# ina_extension_jack_motor_schematic.net
KiCad netlist of a schematic drawn in Altium Designer
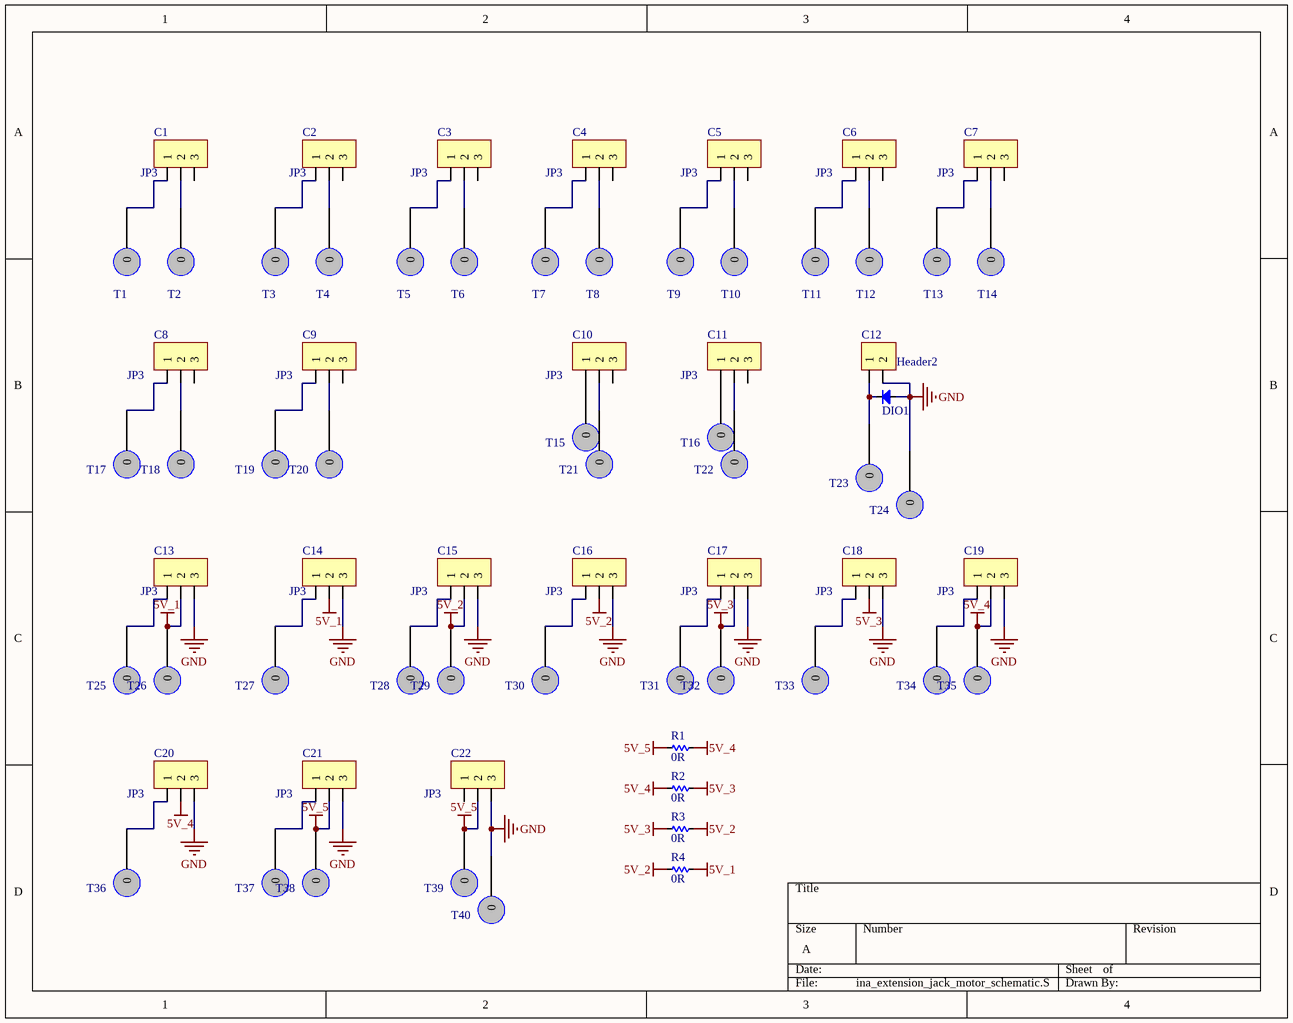
[diagram p0: ina_extension_jack_motor_schematic.SchDoc]

(export (version "E")
  (design (tool "Eeschema 10.0.6"))
  (components
    (comp (ref "C1")
      (value "JP3")
      (footprint "JP3-D1T")
      (description "WR-PHD 2.54 mm Angled Socket Header")
      (fields
        (field (name "MANUFACTURER") "Würth Elektronik eiSos GmbH")
        (field (name "PARTNO") "613003143121")
        (field (name "CREATED BY") "Karrer Zheng")
      )
      (libsource (lib "LIBRARY") (part "JP3"))
    )
    (comp (ref "C2")
      (value "JP3")
      (footprint "JP3-D1T")
      (description "WR-PHD 2.54 mm Angled Socket Header")
      (fields
        (field (name "MANUFACTURER") "Würth Elektronik eiSos GmbH")
        (field (name "PARTNO") "613003143121")
        (field (name "CREATED BY") "Karrer Zheng")
      )
      (libsource (lib "LIBRARY") (part "JP3"))
    )
    (comp (ref "C3")
      (value "JP3")
      (footprint "JP3-D1T")
      (description "WR-PHD 2.54 mm Angled Socket Header")
      (fields
        (field (name "MANUFACTURER") "Würth Elektronik eiSos GmbH")
        (field (name "PARTNO") "613003143121")
        (field (name "CREATED BY") "Karrer Zheng")
      )
      (libsource (lib "LIBRARY") (part "JP3"))
    )
    (comp (ref "C4")
      (value "JP3")
      (footprint "JP3-D1T")
      (description "WR-PHD 2.54 mm Angled Socket Header")
      (fields
        (field (name "MANUFACTURER") "Würth Elektronik eiSos GmbH")
        (field (name "PARTNO") "613003143121")
        (field (name "CREATED BY") "Karrer Zheng")
      )
      (libsource (lib "LIBRARY") (part "JP3"))
    )
    (comp (ref "C5")
      (value "JP3")
      (footprint "JP3-D1T")
      (description "WR-PHD 2.54 mm Angled Socket Header")
      (fields
        (field (name "MANUFACTURER") "Würth Elektronik eiSos GmbH")
        (field (name "PARTNO") "613003143121")
        (field (name "CREATED BY") "Karrer Zheng")
      )
      (libsource (lib "LIBRARY") (part "JP3"))
    )
    (comp (ref "C6")
      (value "JP3")
      (footprint "JP3-D1T")
      (description "WR-PHD 2.54 mm Angled Socket Header")
      (fields
        (field (name "MANUFACTURER") "Würth Elektronik eiSos GmbH")
        (field (name "PARTNO") "613003143121")
        (field (name "CREATED BY") "Karrer Zheng")
      )
      (libsource (lib "LIBRARY") (part "JP3"))
    )
    (comp (ref "C7")
      (value "JP3")
      (footprint "JP3-D1T")
      (description "WR-PHD 2.54 mm Angled Socket Header")
      (fields
        (field (name "MANUFACTURER") "Würth Elektronik eiSos GmbH")
        (field (name "PARTNO") "613003143121")
        (field (name "CREATED BY") "Karrer Zheng")
      )
      (libsource (lib "LIBRARY") (part "JP3"))
    )
    (comp (ref "C8")
      (value "JP3")
      (footprint "JP3-D1T")
      (description "WR-PHD 2.54 mm Angled Socket Header")
      (fields
        (field (name "MANUFACTURER") "Würth Elektronik eiSos GmbH")
        (field (name "PARTNO") "613003143121")
        (field (name "CREATED BY") "Karrer Zheng")
      )
      (libsource (lib "LIBRARY") (part "JP3"))
    )
    (comp (ref "C9")
      (value "JP3")
      (footprint "JP3-D1T")
      (description "WR-PHD 2.54 mm Angled Socket Header")
      (fields
        (field (name "MANUFACTURER") "Würth Elektronik eiSos GmbH")
        (field (name "PARTNO") "613003143121")
        (field (name "CREATED BY") "Karrer Zheng")
      )
      (libsource (lib "LIBRARY") (part "JP3"))
    )
    (comp (ref "C10")
      (value "JP3")
      (footprint "JP3-D1T")
      (description "WR-PHD 2.54 mm Angled Socket Header")
      (fields
        (field (name "MANUFACTURER") "Würth Elektronik eiSos GmbH")
        (field (name "PARTNO") "613003143121")
        (field (name "CREATED BY") "Karrer Zheng")
      )
      (libsource (lib "LIBRARY") (part "JP3"))
    )
    (comp (ref "C11")
      (value "JP3")
      (footprint "JP3-D1T")
      (description "WR-PHD 2.54 mm Angled Socket Header")
      (fields
        (field (name "MANUFACTURER") "Würth Elektronik eiSos GmbH")
        (field (name "PARTNO") "613003143121")
        (field (name "CREATED BY") "Karrer Zheng")
      )
      (libsource (lib "LIBRARY") (part "JP3"))
    )
    (comp (ref "C12")
      (value "Header2")
      (footprint "Header2")
      (description "Header IDC, 2 x 1 Pin Vertical 2.54mm Pitch (Non-Boxed, Male)")
      (fields
        (field (name "MANUFACTURER") "Würth Elektronik eiSos GmbH")
        (field (name "PARTNO") "613002143121")
        (field (name "CREATED BY") "Karrer Zheng")
      )
      (libsource (lib "LIBRARY") (part "Header2"))
    )
    (comp (ref "C13")
      (value "JP3")
      (footprint "JP3-D1T")
      (description "WR-PHD 2.54 mm Angled Socket Header")
      (fields
        (field (name "MANUFACTURER") "Würth Elektronik eiSos GmbH")
        (field (name "PARTNO") "613003143121")
        (field (name "CREATED BY") "Karrer Zheng")
      )
      (libsource (lib "LIBRARY") (part "JP3"))
    )
    (comp (ref "C14")
      (value "JP3")
      (footprint "JP3-D1T")
      (description "WR-PHD 2.54 mm Angled Socket Header")
      (fields
        (field (name "MANUFACTURER") "Würth Elektronik eiSos GmbH")
        (field (name "PARTNO") "613003143121")
        (field (name "CREATED BY") "Karrer Zheng")
      )
      (libsource (lib "LIBRARY") (part "JP3"))
    )
    (comp (ref "C15")
      (value "JP3")
      (footprint "JP3-D1T")
      (description "WR-PHD 2.54 mm Angled Socket Header")
      (fields
        (field (name "MANUFACTURER") "Würth Elektronik eiSos GmbH")
        (field (name "PARTNO") "613003143121")
        (field (name "CREATED BY") "Karrer Zheng")
      )
      (libsource (lib "LIBRARY") (part "JP3"))
    )
    (comp (ref "C16")
      (value "JP3")
      (footprint "JP3-D1T")
      (description "WR-PHD 2.54 mm Angled Socket Header")
      (fields
        (field (name "MANUFACTURER") "Würth Elektronik eiSos GmbH")
        (field (name "PARTNO") "613003143121")
        (field (name "CREATED BY") "Karrer Zheng")
      )
      (libsource (lib "LIBRARY") (part "JP3"))
    )
    (comp (ref "C17")
      (value "JP3")
      (footprint "JP3-D1T")
      (description "WR-PHD 2.54 mm Angled Socket Header")
      (fields
        (field (name "MANUFACTURER") "Würth Elektronik eiSos GmbH")
        (field (name "PARTNO") "613003143121")
        (field (name "CREATED BY") "Karrer Zheng")
      )
      (libsource (lib "LIBRARY") (part "JP3"))
    )
    (comp (ref "C18")
      (value "JP3")
      (footprint "JP3-D1T")
      (description "WR-PHD 2.54 mm Angled Socket Header")
      (fields
        (field (name "MANUFACTURER") "Würth Elektronik eiSos GmbH")
        (field (name "PARTNO") "613003143121")
        (field (name "CREATED BY") "Karrer Zheng")
      )
      (libsource (lib "LIBRARY") (part "JP3"))
    )
    (comp (ref "C19")
      (value "JP3")
      (footprint "JP3-D1T")
      (description "WR-PHD 2.54 mm Angled Socket Header")
      (fields
        (field (name "MANUFACTURER") "Würth Elektronik eiSos GmbH")
        (field (name "PARTNO") "613003143121")
        (field (name "CREATED BY") "Karrer Zheng")
      )
      (libsource (lib "LIBRARY") (part "JP3"))
    )
    (comp (ref "C20")
      (value "JP3")
      (footprint "JP3-D1T")
      (description "WR-PHD 2.54 mm Angled Socket Header")
      (fields
        (field (name "MANUFACTURER") "Würth Elektronik eiSos GmbH")
        (field (name "PARTNO") "613003143121")
        (field (name "CREATED BY") "Karrer Zheng")
      )
      (libsource (lib "LIBRARY") (part "JP3"))
    )
    (comp (ref "C21")
      (value "JP3")
      (footprint "JP3-D1T")
      (description "WR-PHD 2.54 mm Angled Socket Header")
      (fields
        (field (name "MANUFACTURER") "Würth Elektronik eiSos GmbH")
        (field (name "PARTNO") "613003143121")
        (field (name "CREATED BY") "Karrer Zheng")
      )
      (libsource (lib "LIBRARY") (part "JP3"))
    )
    (comp (ref "C22")
      (value "JP3")
      (footprint "JP3-D1T")
      (description "WR-PHD 2.54 mm Angled Socket Header")
      (fields
        (field (name "MANUFACTURER") "Würth Elektronik eiSos GmbH")
        (field (name "PARTNO") "613003143121")
        (field (name "CREATED BY") "Karrer Zheng")
      )
      (libsource (lib "LIBRARY") (part "JP3"))
    )
    (comp (ref "DIO1")
      (value "Diode SMD")
      (footprint "DIO-SMD-123")
      (description "Default Diode")
      (fields (field (name "PUBLISHER") "Altium Limited"))
      (libsource (lib "LIBRARY") (part "Diode SMD"))
    )
    (comp (ref "R1")
      (value "0R")
      (footprint "RES-SMD-0603")
      (description "Resistor")
      (fields
        (field (name "MANUFACTURER") "Generic Components")
        (field (name "PUBLISHER") "Altium Hobart Technology Centre")
      )
      (libsource (lib "LIBRARY") (part "Res-SMD"))
    )
    (comp (ref "R2")
      (value "0R")
      (footprint "RES-SMD-0603")
      (description "Resistor")
      (fields
        (field (name "MANUFACTURER") "Generic Components")
        (field (name "PUBLISHER") "Altium Hobart Technology Centre")
      )
      (libsource (lib "LIBRARY") (part "Res-SMD"))
    )
    (comp (ref "R3")
      (value "0R")
      (footprint "RES-SMD-0603")
      (description "Resistor")
      (fields
        (field (name "MANUFACTURER") "Generic Components")
        (field (name "PUBLISHER") "Altium Hobart Technology Centre")
      )
      (libsource (lib "LIBRARY") (part "Res-SMD"))
    )
    (comp (ref "R4")
      (value "0R")
      (footprint "RES-SMD-0603")
      (description "Resistor")
      (fields
        (field (name "MANUFACTURER") "Generic Components")
        (field (name "PUBLISHER") "Altium Hobart Technology Centre")
      )
      (libsource (lib "LIBRARY") (part "Res-SMD"))
    )
    (comp (ref "T1")
      (value "Pad")
      (footprint "pad_ina:PCBComponent_1")
      (description "pad")
      (libsource (lib "pad_ina") (part "Component_1"))
    )
    (comp (ref "T2")
      (value "Pad")
      (footprint "pad_ina:PCBComponent_1")
      (description "pad")
      (libsource (lib "pad_ina") (part "Component_1"))
    )
    (comp (ref "T3")
      (value "Pad")
      (footprint "pad_ina:PCBComponent_1")
      (description "pad")
      (libsource (lib "pad_ina") (part "Component_1"))
    )
    (comp (ref "T4")
      (value "Pad")
      (footprint "pad_ina:PCBComponent_1")
      (description "pad")
      (libsource (lib "pad_ina") (part "Component_1"))
    )
    (comp (ref "T5")
      (value "Pad")
      (footprint "pad_ina:PCBComponent_1")
      (description "pad")
      (libsource (lib "pad_ina") (part "Component_1"))
    )
    (comp (ref "T6")
      (value "Pad")
      (footprint "pad_ina:PCBComponent_1")
      (description "pad")
      (libsource (lib "pad_ina") (part "Component_1"))
    )
    (comp (ref "T7")
      (value "Pad")
      (footprint "pad_ina:PCBComponent_1")
      (description "pad")
      (libsource (lib "pad_ina") (part "Component_1"))
    )
    (comp (ref "T8")
      (value "Pad")
      (footprint "pad_ina:PCBComponent_1")
      (description "pad")
      (libsource (lib "pad_ina") (part "Component_1"))
    )
    (comp (ref "T9")
      (value "Pad")
      (footprint "pad_ina:PCBComponent_1")
      (description "pad")
      (libsource (lib "pad_ina") (part "Component_1"))
    )
    (comp (ref "T10")
      (value "Pad")
      (footprint "pad_ina:PCBComponent_1")
      (description "pad")
      (libsource (lib "pad_ina") (part "Component_1"))
    )
    (comp (ref "T11")
      (value "Pad")
      (footprint "pad_ina:PCBComponent_1")
      (description "pad")
      (libsource (lib "pad_ina") (part "Component_1"))
    )
    (comp (ref "T12")
      (value "Pad")
      (footprint "pad_ina:PCBComponent_1")
      (description "pad")
      (libsource (lib "pad_ina") (part "Component_1"))
    )
    (comp (ref "T13")
      (value "Pad")
      (footprint "pad_ina:PCBComponent_1")
      (description "pad")
      (libsource (lib "pad_ina") (part "Component_1"))
    )
    (comp (ref "T14")
      (value "Pad")
      (footprint "pad_ina:PCBComponent_1")
      (description "pad")
      (libsource (lib "pad_ina") (part "Component_1"))
    )
    (comp (ref "T15")
      (value "Pad")
      (footprint "pad_ina:PCBComponent_1")
      (description "pad")
      (libsource (lib "pad_ina") (part "Component_1"))
    )
    (comp (ref "T16")
      (value "Pad")
      (footprint "pad_ina:PCBComponent_1")
      (description "pad")
      (libsource (lib "pad_ina") (part "Component_1"))
    )
    (comp (ref "T17")
      (value "Pad")
      (footprint "pad_ina:PCBComponent_1")
      (description "pad")
      (libsource (lib "pad_ina") (part "Component_1"))
    )
    (comp (ref "T18")
      (value "Pad")
      (footprint "pad_ina:PCBComponent_1")
      (description "pad")
      (libsource (lib "pad_ina") (part "Component_1"))
    )
    (comp (ref "T19")
      (value "Pad")
      (footprint "pad_ina:PCBComponent_1")
      (description "pad")
      (libsource (lib "pad_ina") (part "Component_1"))
    )
    (comp (ref "T20")
      (value "Pad")
      (footprint "pad_ina:PCBComponent_1")
      (description "pad")
      (libsource (lib "pad_ina") (part "Component_1"))
    )
    (comp (ref "T21")
      (value "Pad")
      (footprint "pad_ina:PCBComponent_1")
      (description "pad")
      (libsource (lib "pad_ina") (part "Component_1"))
    )
    (comp (ref "T22")
      (value "Pad")
      (footprint "pad_ina:PCBComponent_1")
      (description "pad")
      (libsource (lib "pad_ina") (part "Component_1"))
    )
    (comp (ref "T23")
      (value "Pad")
      (footprint "pad_ina:PCBComponent_1")
      (description "pad")
      (libsource (lib "pad_ina") (part "Component_1"))
    )
    (comp (ref "T24")
      (value "Pad")
      (footprint "pad_ina:PCBComponent_1")
      (description "pad")
      (libsource (lib "pad_ina") (part "Component_1"))
    )
    (comp (ref "T25")
      (value "Pad")
      (footprint "pad_ina:PCBComponent_1")
      (description "pad")
      (libsource (lib "pad_ina") (part "Component_1"))
    )
    (comp (ref "T26")
      (value "Pad")
      (footprint "pad_ina:PCBComponent_1")
      (description "pad")
      (libsource (lib "pad_ina") (part "Component_1"))
    )
    (comp (ref "T27")
      (value "Pad")
      (footprint "pad_ina:PCBComponent_1")
      (description "pad")
      (libsource (lib "pad_ina") (part "Component_1"))
    )
    (comp (ref "T28")
      (value "Pad")
      (footprint "pad_ina:PCBComponent_1")
      (description "pad")
      (libsource (lib "pad_ina") (part "Component_1"))
    )
    (comp (ref "T29")
      (value "Pad")
      (footprint "pad_ina:PCBComponent_1")
      (description "pad")
      (libsource (lib "pad_ina") (part "Component_1"))
    )
    (comp (ref "T30")
      (value "Pad")
      (footprint "pad_ina:PCBComponent_1")
      (description "pad")
      (libsource (lib "pad_ina") (part "Component_1"))
    )
    (comp (ref "T31")
      (value "Pad")
      (footprint "pad_ina:PCBComponent_1")
      (description "pad")
      (libsource (lib "pad_ina") (part "Component_1"))
    )
    (comp (ref "T32")
      (value "Pad")
      (footprint "pad_ina:PCBComponent_1")
      (description "pad")
      (libsource (lib "pad_ina") (part "Component_1"))
    )
    (comp (ref "T33")
      (value "Pad")
      (footprint "pad_ina:PCBComponent_1")
      (description "pad")
      (libsource (lib "pad_ina") (part "Component_1"))
    )
    (comp (ref "T34")
      (value "Pad")
      (footprint "pad_ina:PCBComponent_1")
      (description "pad")
      (libsource (lib "pad_ina") (part "Component_1"))
    )
    (comp (ref "T35")
      (value "Pad")
      (footprint "pad_ina:PCBComponent_1")
      (description "pad")
      (libsource (lib "pad_ina") (part "Component_1"))
    )
    (comp (ref "T36")
      (value "Pad")
      (footprint "pad_ina:PCBComponent_1")
      (description "pad")
      (libsource (lib "pad_ina") (part "Component_1"))
    )
    (comp (ref "T37")
      (value "Pad")
      (footprint "pad_ina:PCBComponent_1")
      (description "pad")
      (libsource (lib "pad_ina") (part "Component_1"))
    )
    (comp (ref "T38")
      (value "Pad")
      (footprint "pad_ina:PCBComponent_1")
      (description "pad")
      (libsource (lib "pad_ina") (part "Component_1"))
    )
    (comp (ref "T39")
      (value "Pad")
      (footprint "pad_ina:PCBComponent_1")
      (description "pad")
      (libsource (lib "pad_ina") (part "Component_1"))
    )
    (comp (ref "T40")
      (value "Pad")
      (footprint "pad_ina:PCBComponent_1")
      (description "pad")
      (libsource (lib "pad_ina") (part "Component_1"))
    )
  )
  (nets
    (net (code "1") (name "5V_1") (class "Default")
      (node (ref "C13") (pin "2") (pinfunction "2_2") (pintype "passive"))
      (node (ref "C14") (pin "2") (pinfunction "2_2") (pintype "passive"))
      (node (ref "R4") (pin "2") (pinfunction "2_2") (pintype "passive"))
      (node (ref "T26") (pin "0") (pinfunction "0_0") (pintype "passive"))
    )
    (net (code "2") (name "5V_2") (class "Default")
      (node (ref "C15") (pin "2") (pinfunction "2_2") (pintype "passive"))
      (node (ref "C16") (pin "2") (pinfunction "2_2") (pintype "passive"))
      (node (ref "R3") (pin "2") (pinfunction "2_2") (pintype "passive"))
      (node (ref "R4") (pin "1") (pinfunction "1_1") (pintype "passive"))
      (node (ref "T29") (pin "0") (pinfunction "0_0") (pintype "passive"))
    )
    (net (code "3") (name "5V_3") (class "Default")
      (node (ref "C17") (pin "2") (pinfunction "2_2") (pintype "passive"))
      (node (ref "C18") (pin "2") (pinfunction "2_2") (pintype "passive"))
      (node (ref "R2") (pin "2") (pinfunction "2_2") (pintype "passive"))
      (node (ref "R3") (pin "1") (pinfunction "1_1") (pintype "passive"))
      (node (ref "T32") (pin "0") (pinfunction "0_0") (pintype "passive"))
    )
    (net (code "4") (name "5V_4") (class "Default")
      (node (ref "C19") (pin "2") (pinfunction "2_2") (pintype "passive"))
      (node (ref "C20") (pin "2") (pinfunction "2_2") (pintype "passive"))
      (node (ref "R1") (pin "2") (pinfunction "2_2") (pintype "passive"))
      (node (ref "R2") (pin "1") (pinfunction "1_1") (pintype "passive"))
      (node (ref "T35") (pin "0") (pinfunction "0_0") (pintype "passive"))
    )
    (net (code "5") (name "5V_5") (class "Default")
      (node (ref "C21") (pin "2") (pinfunction "2_2") (pintype "passive"))
      (node (ref "C22") (pin "2") (pinfunction "2_2") (pintype "passive"))
      (node (ref "R1") (pin "1") (pinfunction "1_1") (pintype "passive"))
      (node (ref "T38") (pin "0") (pinfunction "0_0") (pintype "passive"))
      (node (ref "T39") (pin "0") (pinfunction "0_0") (pintype "passive"))
    )
    (net (code "6") (name "GND") (class "Default")
      (node (ref "C12") (pin "2") (pinfunction "2_2") (pintype "passive"))
      (node (ref "C13") (pin "3") (pinfunction "3_3") (pintype "passive"))
      (node (ref "C14") (pin "3") (pinfunction "3_3") (pintype "passive"))
      (node (ref "C15") (pin "3") (pinfunction "3_3") (pintype "passive"))
      (node (ref "C16") (pin "3") (pinfunction "3_3") (pintype "passive"))
      (node (ref "C17") (pin "3") (pinfunction "3_3") (pintype "passive"))
      (node (ref "C18") (pin "3") (pinfunction "3_3") (pintype "passive"))
      (node (ref "C19") (pin "3") (pinfunction "3_3") (pintype "passive"))
      (node (ref "C20") (pin "3") (pinfunction "3_3") (pintype "passive"))
      (node (ref "C21") (pin "3") (pinfunction "3_3") (pintype "passive"))
      (node (ref "C22") (pin "3") (pinfunction "3_3") (pintype "passive"))
      (node (ref "DIO1") (pin "1") (pinfunction "A_1") (pintype "passive"))
      (node (ref "T24") (pin "0") (pinfunction "0_0") (pintype "passive"))
      (node (ref "T40") (pin "0") (pinfunction "0_0") (pintype "passive"))
    )
    (net (code "7") (name "Net-(C1-Pad1)") (class "Default")
      (node (ref "C1") (pin "1") (pinfunction "1_1") (pintype "passive"))
      (node (ref "T1") (pin "0") (pinfunction "0_0") (pintype "passive"))
    )
    (net (code "8") (name "Net-(C1-Pad2)") (class "Default")
      (node (ref "C1") (pin "2") (pinfunction "2_2") (pintype "passive"))
      (node (ref "T2") (pin "0") (pinfunction "0_0") (pintype "passive"))
    )
    (net (code "9") (name "Net-(C2-Pad1)") (class "Default")
      (node (ref "C2") (pin "1") (pinfunction "1_1") (pintype "passive"))
      (node (ref "T3") (pin "0") (pinfunction "0_0") (pintype "passive"))
    )
    (net (code "10") (name "Net-(C2-Pad2)") (class "Default")
      (node (ref "C2") (pin "2") (pinfunction "2_2") (pintype "passive"))
      (node (ref "T4") (pin "0") (pinfunction "0_0") (pintype "passive"))
    )
    (net (code "11") (name "Net-(C3-Pad1)") (class "Default")
      (node (ref "C3") (pin "1") (pinfunction "1_1") (pintype "passive"))
      (node (ref "T5") (pin "0") (pinfunction "0_0") (pintype "passive"))
    )
    (net (code "12") (name "Net-(C3-Pad2)") (class "Default")
      (node (ref "C3") (pin "2") (pinfunction "2_2") (pintype "passive"))
      (node (ref "T6") (pin "0") (pinfunction "0_0") (pintype "passive"))
    )
    (net (code "13") (name "Net-(C4-Pad1)") (class "Default")
      (node (ref "C4") (pin "1") (pinfunction "1_1") (pintype "passive"))
      (node (ref "T7") (pin "0") (pinfunction "0_0") (pintype "passive"))
    )
    (net (code "14") (name "Net-(C4-Pad2)") (class "Default")
      (node (ref "C4") (pin "2") (pinfunction "2_2") (pintype "passive"))
      (node (ref "T8") (pin "0") (pinfunction "0_0") (pintype "passive"))
    )
    (net (code "15") (name "Net-(C5-Pad1)") (class "Default")
      (node (ref "C5") (pin "1") (pinfunction "1_1") (pintype "passive"))
      (node (ref "T9") (pin "0") (pinfunction "0_0") (pintype "passive"))
    )
    (net (code "16") (name "Net-(C5-Pad2)") (class "Default")
      (node (ref "C5") (pin "2") (pinfunction "2_2") (pintype "passive"))
      (node (ref "T10") (pin "0") (pinfunction "0_0") (pintype "passive"))
    )
    (net (code "17") (name "Net-(C6-Pad1)") (class "Default")
      (node (ref "C6") (pin "1") (pinfunction "1_1") (pintype "passive"))
      (node (ref "T11") (pin "0") (pinfunction "0_0") (pintype "passive"))
    )
    (net (code "18") (name "Net-(C6-Pad2)") (class "Default")
      (node (ref "C6") (pin "2") (pinfunction "2_2") (pintype "passive"))
      (node (ref "T12") (pin "0") (pinfunction "0_0") (pintype "passive"))
    )
    (net (code "19") (name "Net-(C7-Pad1)") (class "Default")
      (node (ref "C7") (pin "1") (pinfunction "1_1") (pintype "passive"))
      (node (ref "T13") (pin "0") (pinfunction "0_0") (pintype "passive"))
    )
    (net (code "20") (name "Net-(C7-Pad2)") (class "Default")
      (node (ref "C7") (pin "2") (pinfunction "2_2") (pintype "passive"))
      (node (ref "T14") (pin "0") (pinfunction "0_0") (pintype "passive"))
    )
    (net (code "21") (name "Net-(C8-Pad1)") (class "Default")
      (node (ref "C8") (pin "1") (pinfunction "1_1") (pintype "passive"))
      (node (ref "T17") (pin "0") (pinfunction "0_0") (pintype "passive"))
    )
    (net (code "22") (name "Net-(C8-Pad2)") (class "Default")
      (node (ref "C8") (pin "2") (pinfunction "2_2") (pintype "passive"))
      (node (ref "T18") (pin "0") (pinfunction "0_0") (pintype "passive"))
    )
    (net (code "23") (name "Net-(C9-Pad1)") (class "Default")
      (node (ref "C9") (pin "1") (pinfunction "1_1") (pintype "passive"))
      (node (ref "T19") (pin "0") (pinfunction "0_0") (pintype "passive"))
    )
    (net (code "24") (name "Net-(C9-Pad2)") (class "Default")
      (node (ref "C9") (pin "2") (pinfunction "2_2") (pintype "passive"))
      (node (ref "T20") (pin "0") (pinfunction "0_0") (pintype "passive"))
    )
    (net (code "25") (name "Net-(C10-Pad1)") (class "Default")
      (node (ref "C10") (pin "1") (pinfunction "1_1") (pintype "passive"))
      (node (ref "T15") (pin "0") (pinfunction "0_0") (pintype "passive"))
    )
    (net (code "26") (name "Net-(C10-Pad2)") (class "Default")
      (node (ref "C10") (pin "2") (pinfunction "2_2") (pintype "passive"))
      (node (ref "T21") (pin "0") (pinfunction "0_0") (pintype "passive"))
    )
    (net (code "27") (name "Net-(C11-Pad1)") (class "Default")
      (node (ref "C11") (pin "1") (pinfunction "1_1") (pintype "passive"))
      (node (ref "T16") (pin "0") (pinfunction "0_0") (pintype "passive"))
    )
    (net (code "28") (name "Net-(C11-Pad2)") (class "Default")
      (node (ref "C11") (pin "2") (pinfunction "2_2") (pintype "passive"))
      (node (ref "T22") (pin "0") (pinfunction "0_0") (pintype "passive"))
    )
    (net (code "29") (name "Net-(C13-Pad1)") (class "Default")
      (node (ref "C13") (pin "1") (pinfunction "1_1") (pintype "passive"))
      (node (ref "T25") (pin "0") (pinfunction "0_0") (pintype "passive"))
    )
    (net (code "30") (name "Net-(C14-Pad1)") (class "Default")
      (node (ref "C14") (pin "1") (pinfunction "1_1") (pintype "passive"))
      (node (ref "T27") (pin "0") (pinfunction "0_0") (pintype "passive"))
    )
    (net (code "31") (name "Net-(C15-Pad1)") (class "Default")
      (node (ref "C15") (pin "1") (pinfunction "1_1") (pintype "passive"))
      (node (ref "T28") (pin "0") (pinfunction "0_0") (pintype "passive"))
    )
    (net (code "32") (name "Net-(C16-Pad1)") (class "Default")
      (node (ref "C16") (pin "1") (pinfunction "1_1") (pintype "passive"))
      (node (ref "T30") (pin "0") (pinfunction "0_0") (pintype "passive"))
    )
    (net (code "33") (name "Net-(C17-Pad1)") (class "Default")
      (node (ref "C17") (pin "1") (pinfunction "1_1") (pintype "passive"))
      (node (ref "T31") (pin "0") (pinfunction "0_0") (pintype "passive"))
    )
    (net (code "34") (name "Net-(C18-Pad1)") (class "Default")
      (node (ref "C18") (pin "1") (pinfunction "1_1") (pintype "passive"))
      (node (ref "T33") (pin "0") (pinfunction "0_0") (pintype "passive"))
    )
    (net (code "35") (name "Net-(C19-Pad1)") (class "Default")
      (node (ref "C19") (pin "1") (pinfunction "1_1") (pintype "passive"))
      (node (ref "T34") (pin "0") (pinfunction "0_0") (pintype "passive"))
    )
    (net (code "36") (name "Net-(C20-Pad1)") (class "Default")
      (node (ref "C20") (pin "1") (pinfunction "1_1") (pintype "passive"))
      (node (ref "T36") (pin "0") (pinfunction "0_0") (pintype "passive"))
    )
    (net (code "37") (name "Net-(C21-Pad1)") (class "Default")
      (node (ref "C21") (pin "1") (pinfunction "1_1") (pintype "passive"))
      (node (ref "T37") (pin "0") (pinfunction "0_0") (pintype "passive"))
    )
    (net (code "38") (name "Net-(DIO1-K)") (class "Default")
      (node (ref "C12") (pin "1") (pinfunction "1_1") (pintype "passive"))
      (node (ref "DIO1") (pin "2") (pinfunction "K_2") (pintype "passive"))
      (node (ref "T23") (pin "0") (pinfunction "0_0") (pintype "passive"))
    )
    (net (code "39") (name "unconnected-(C1-Pad3)") (class "Default")
      (node (ref "C1") (pin "3") (pinfunction "3_3") (pintype "passive"))
    )
    (net (code "40") (name "unconnected-(C2-Pad3)") (class "Default")
      (node (ref "C2") (pin "3") (pinfunction "3_3") (pintype "passive"))
    )
    (net (code "41") (name "unconnected-(C3-Pad3)") (class "Default")
      (node (ref "C3") (pin "3") (pinfunction "3_3") (pintype "passive"))
    )
    (net (code "42") (name "unconnected-(C4-Pad3)") (class "Default")
      (node (ref "C4") (pin "3") (pinfunction "3_3") (pintype "passive"))
    )
    (net (code "43") (name "unconnected-(C5-Pad3)") (class "Default")
      (node (ref "C5") (pin "3") (pinfunction "3_3") (pintype "passive"))
    )
    (net (code "44") (name "unconnected-(C6-Pad3)") (class "Default")
      (node (ref "C6") (pin "3") (pinfunction "3_3") (pintype "passive"))
    )
    (net (code "45") (name "unconnected-(C7-Pad3)") (class "Default")
      (node (ref "C7") (pin "3") (pinfunction "3_3") (pintype "passive"))
    )
    (net (code "46") (name "unconnected-(C8-Pad3)") (class "Default")
      (node (ref "C8") (pin "3") (pinfunction "3_3") (pintype "passive"))
    )
    (net (code "47") (name "unconnected-(C9-Pad3)") (class "Default")
      (node (ref "C9") (pin "3") (pinfunction "3_3") (pintype "passive"))
    )
    (net (code "48") (name "unconnected-(C10-Pad3)") (class "Default")
      (node (ref "C10") (pin "3") (pinfunction "3_3") (pintype "passive"))
    )
    (net (code "49") (name "unconnected-(C11-Pad3)") (class "Default")
      (node (ref "C11") (pin "3") (pinfunction "3_3") (pintype "passive"))
    )
    (net (code "50") (name "unconnected-(C22-Pad1)") (class "Default")
      (node (ref "C22") (pin "1") (pinfunction "1_1") (pintype "passive"))
    )
  )
)
